# colorCube64_led1.net
KiCad netlist of a schematic drawn in EAGLE
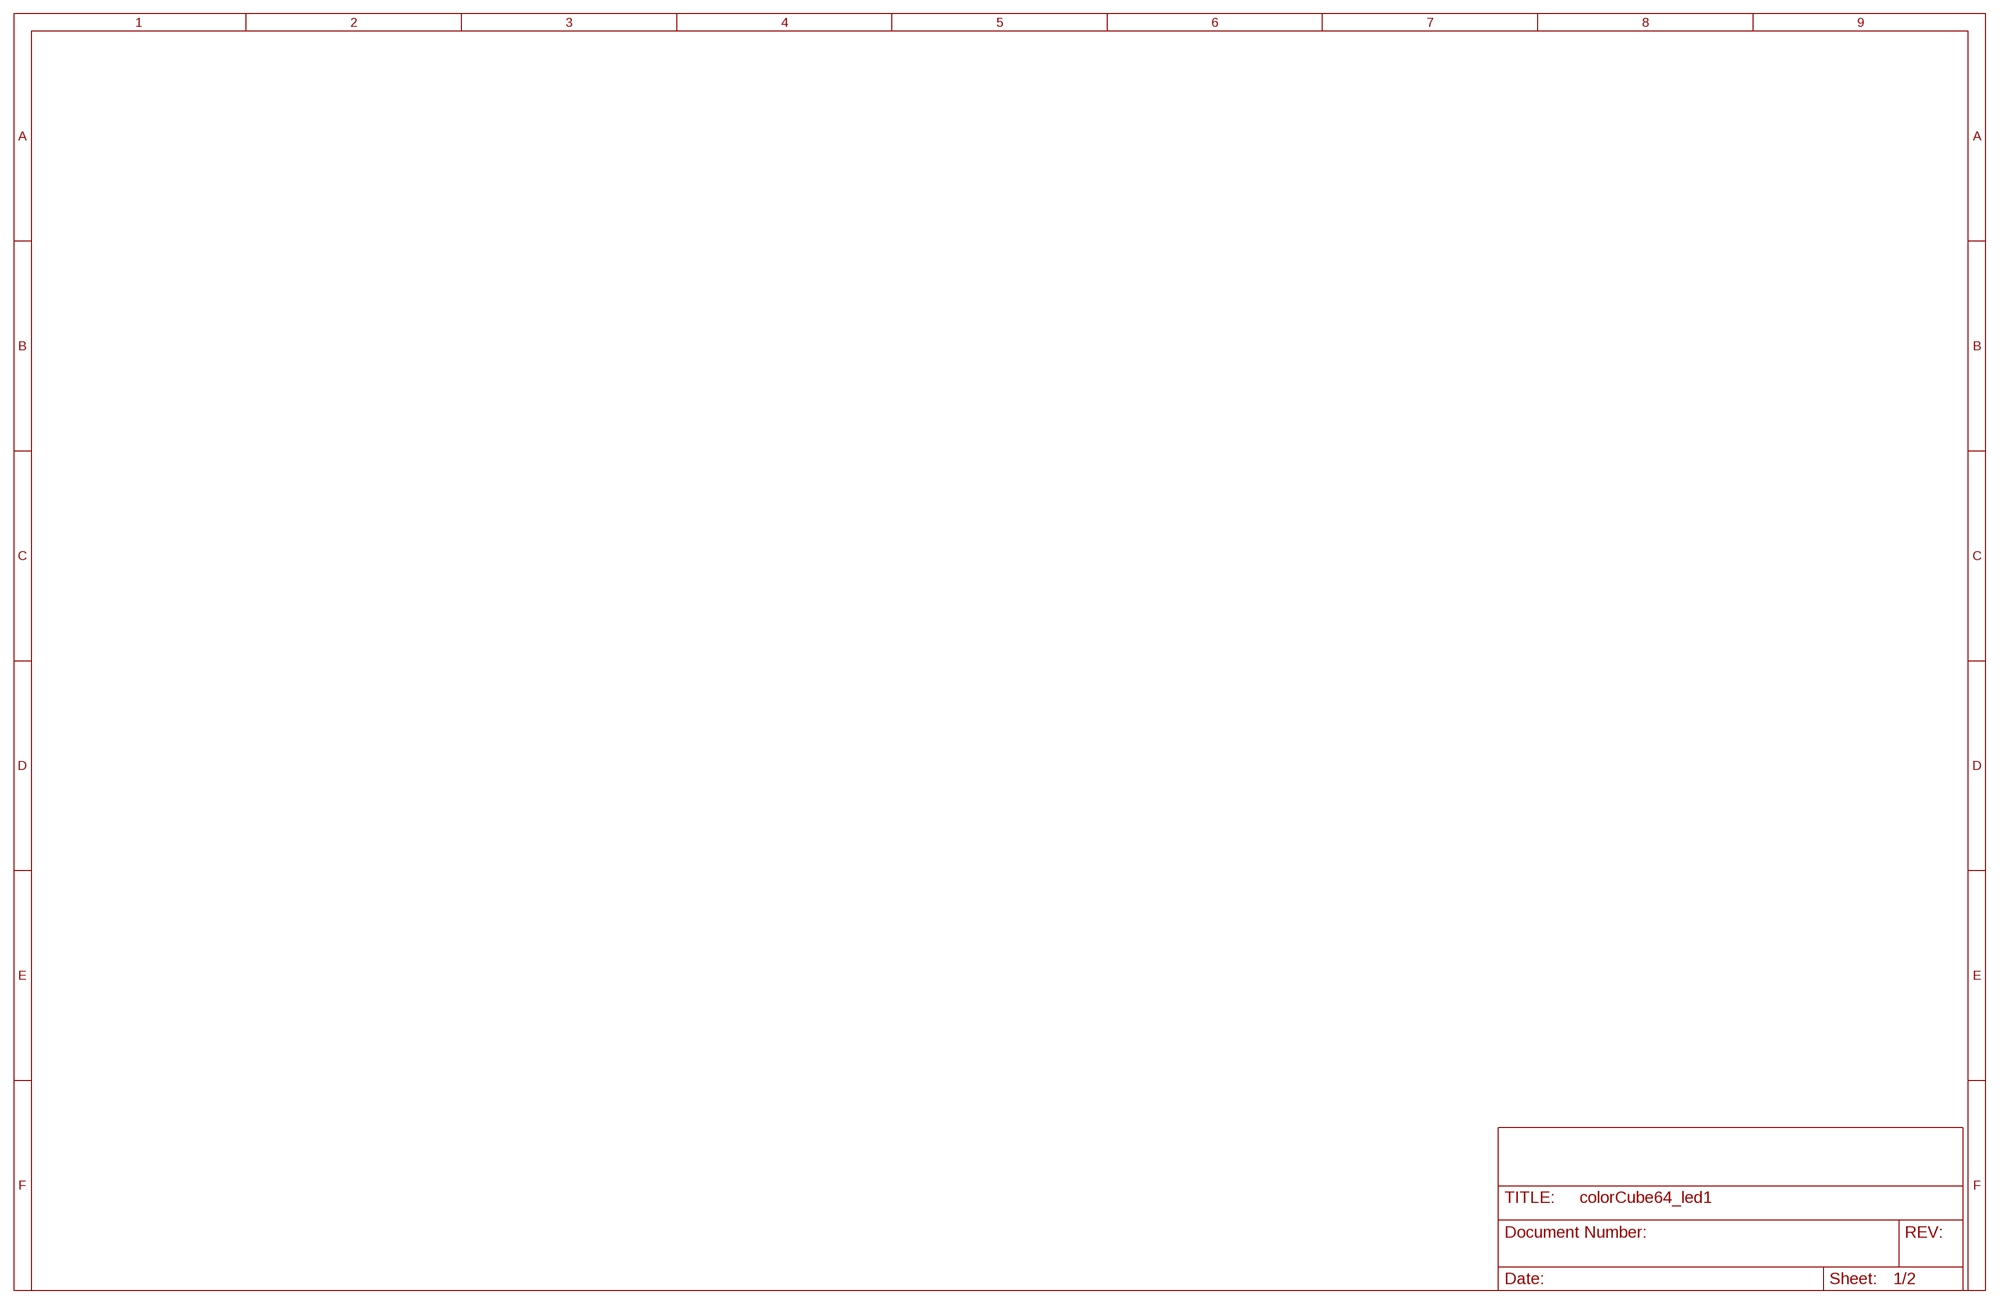
[diagram p0: schematic, sheet 1]
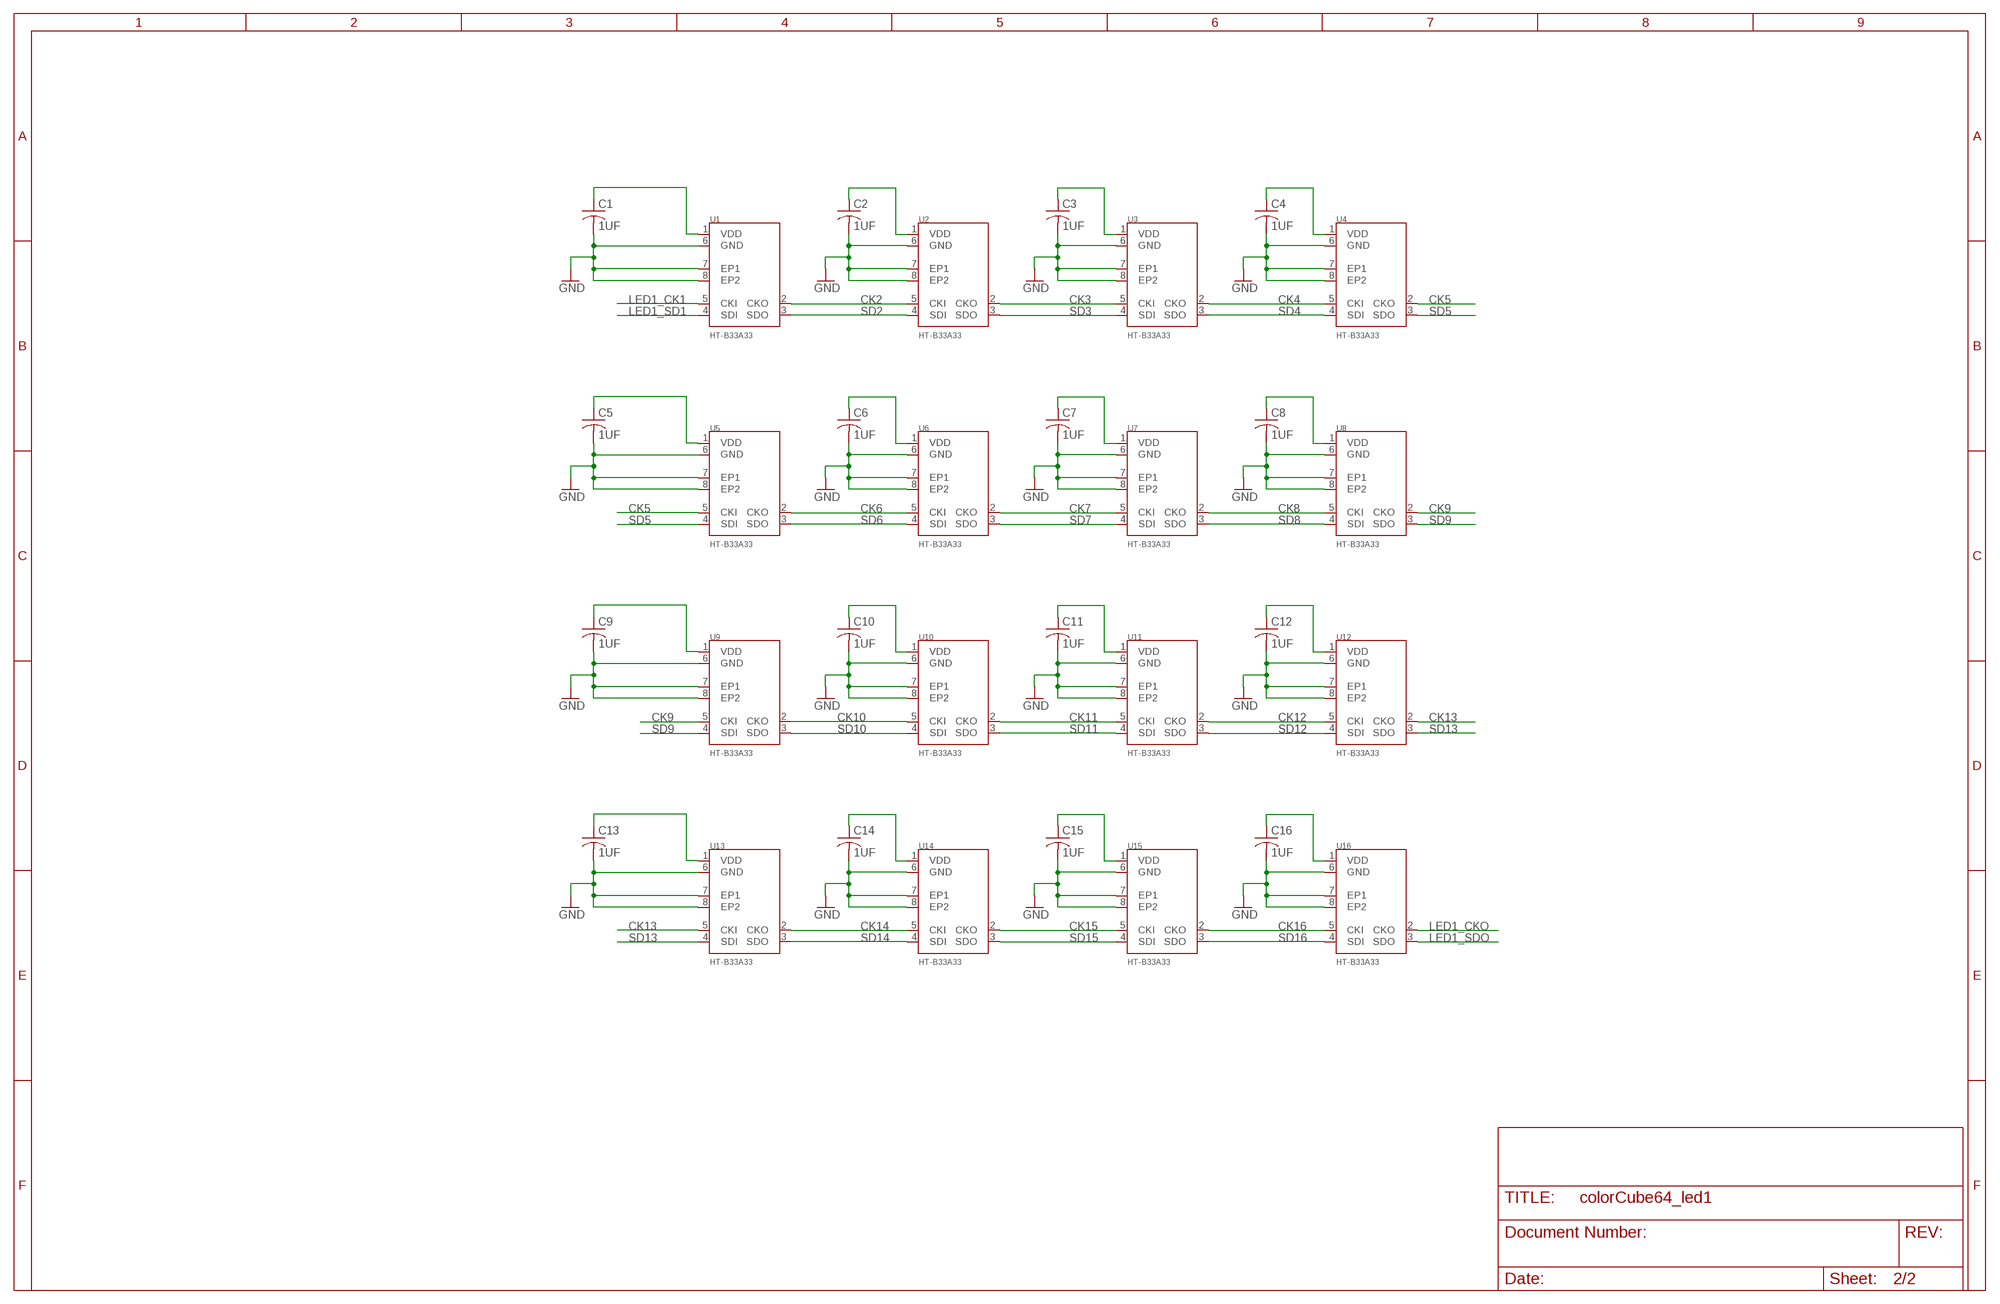
[diagram p1: schematic, sheet 2]

(export (version "E")
  (design (tool "Eeschema 10.0.6"))
  (components
    (comp (ref "C1")
      (value "1UF")
      (footprint "eagle-import:C0201")
      (libsource (lib "eagle-import") (part "C-USC0201"))
    )
    (comp (ref "C2")
      (value "1UF")
      (footprint "eagle-import:C0201")
      (libsource (lib "eagle-import") (part "C-USC0201"))
    )
    (comp (ref "C3")
      (value "1UF")
      (footprint "eagle-import:C0201")
      (libsource (lib "eagle-import") (part "C-USC0201"))
    )
    (comp (ref "C4")
      (value "1UF")
      (footprint "eagle-import:C0201")
      (libsource (lib "eagle-import") (part "C-USC0201"))
    )
    (comp (ref "C5")
      (value "1UF")
      (footprint "eagle-import:C0201")
      (libsource (lib "eagle-import") (part "C-USC0201"))
    )
    (comp (ref "C6")
      (value "1UF")
      (footprint "eagle-import:C0201")
      (libsource (lib "eagle-import") (part "C-USC0201"))
    )
    (comp (ref "C7")
      (value "1UF")
      (footprint "eagle-import:C0201")
      (libsource (lib "eagle-import") (part "C-USC0201"))
    )
    (comp (ref "C8")
      (value "1UF")
      (footprint "eagle-import:C0201")
      (libsource (lib "eagle-import") (part "C-USC0201"))
    )
    (comp (ref "C9")
      (value "1UF")
      (footprint "eagle-import:C0201")
      (libsource (lib "eagle-import") (part "C-USC0201"))
    )
    (comp (ref "C10")
      (value "1UF")
      (footprint "eagle-import:C0201")
      (libsource (lib "eagle-import") (part "C-USC0201"))
    )
    (comp (ref "C11")
      (value "1UF")
      (footprint "eagle-import:C0201")
      (libsource (lib "eagle-import") (part "C-USC0201"))
    )
    (comp (ref "C12")
      (value "1UF")
      (footprint "eagle-import:C0201")
      (libsource (lib "eagle-import") (part "C-USC0201"))
    )
    (comp (ref "C13")
      (value "1UF")
      (footprint "eagle-import:C0201")
      (libsource (lib "eagle-import") (part "C-USC0201"))
    )
    (comp (ref "C14")
      (value "1UF")
      (footprint "eagle-import:C0201")
      (libsource (lib "eagle-import") (part "C-USC0201"))
    )
    (comp (ref "C15")
      (value "1UF")
      (footprint "eagle-import:C0201")
      (libsource (lib "eagle-import") (part "C-USC0201"))
    )
    (comp (ref "C16")
      (value "1UF")
      (footprint "eagle-import:C0201")
      (libsource (lib "eagle-import") (part "C-USC0201"))
    )
    (comp (ref "U1")
      (value "HT-B33A33")
      (footprint "eagle-import:HT-B33A3")
      (libsource (lib "eagle-import") (part "HT-B33A33"))
    )
    (comp (ref "U2")
      (value "HT-B33A33")
      (footprint "eagle-import:HT-B33A3")
      (libsource (lib "eagle-import") (part "HT-B33A33"))
    )
    (comp (ref "U3")
      (value "HT-B33A33")
      (footprint "eagle-import:HT-B33A3")
      (libsource (lib "eagle-import") (part "HT-B33A33"))
    )
    (comp (ref "U4")
      (value "HT-B33A33")
      (footprint "eagle-import:HT-B33A3")
      (libsource (lib "eagle-import") (part "HT-B33A33"))
    )
    (comp (ref "U5")
      (value "HT-B33A33")
      (footprint "eagle-import:HT-B33A3")
      (libsource (lib "eagle-import") (part "HT-B33A33"))
    )
    (comp (ref "U6")
      (value "HT-B33A33")
      (footprint "eagle-import:HT-B33A3")
      (libsource (lib "eagle-import") (part "HT-B33A33"))
    )
    (comp (ref "U7")
      (value "HT-B33A33")
      (footprint "eagle-import:HT-B33A3")
      (libsource (lib "eagle-import") (part "HT-B33A33"))
    )
    (comp (ref "U8")
      (value "HT-B33A33")
      (footprint "eagle-import:HT-B33A3")
      (libsource (lib "eagle-import") (part "HT-B33A33"))
    )
    (comp (ref "U9")
      (value "HT-B33A33")
      (footprint "eagle-import:HT-B33A3")
      (libsource (lib "eagle-import") (part "HT-B33A33"))
    )
    (comp (ref "U10")
      (value "HT-B33A33")
      (footprint "eagle-import:HT-B33A3")
      (libsource (lib "eagle-import") (part "HT-B33A33"))
    )
    (comp (ref "U11")
      (value "HT-B33A33")
      (footprint "eagle-import:HT-B33A3")
      (libsource (lib "eagle-import") (part "HT-B33A33"))
    )
    (comp (ref "U12")
      (value "HT-B33A33")
      (footprint "eagle-import:HT-B33A3")
      (libsource (lib "eagle-import") (part "HT-B33A33"))
    )
    (comp (ref "U13")
      (value "HT-B33A33")
      (footprint "eagle-import:HT-B33A3")
      (libsource (lib "eagle-import") (part "HT-B33A33"))
    )
    (comp (ref "U14")
      (value "HT-B33A33")
      (footprint "eagle-import:HT-B33A3")
      (libsource (lib "eagle-import") (part "HT-B33A33"))
    )
    (comp (ref "U15")
      (value "HT-B33A33")
      (footprint "eagle-import:HT-B33A3")
      (libsource (lib "eagle-import") (part "HT-B33A33"))
    )
    (comp (ref "U16")
      (value "HT-B33A33")
      (footprint "eagle-import:HT-B33A3")
      (libsource (lib "eagle-import") (part "HT-B33A33"))
    )
  )
  (nets
    (net (code "1") (name "CK2") (class "Default")
      (node (ref "U1") (pin "2") (pinfunction "CKO_2") (pintype "bidirectional"))
      (node (ref "U2") (pin "5") (pinfunction "CKI_5") (pintype "bidirectional"))
    )
    (net (code "2") (name "CK3") (class "Default")
      (node (ref "U2") (pin "2") (pinfunction "CKO_2") (pintype "bidirectional"))
      (node (ref "U3") (pin "5") (pinfunction "CKI_5") (pintype "bidirectional"))
    )
    (net (code "3") (name "CK4") (class "Default")
      (node (ref "U3") (pin "2") (pinfunction "CKO_2") (pintype "bidirectional"))
      (node (ref "U4") (pin "5") (pinfunction "CKI_5") (pintype "bidirectional"))
    )
    (net (code "4") (name "CK5") (class "Default")
      (node (ref "U4") (pin "2") (pinfunction "CKO_2") (pintype "bidirectional"))
      (node (ref "U5") (pin "5") (pinfunction "CKI_5") (pintype "bidirectional"))
    )
    (net (code "5") (name "CK6") (class "Default")
      (node (ref "U5") (pin "2") (pinfunction "CKO_2") (pintype "bidirectional"))
      (node (ref "U6") (pin "5") (pinfunction "CKI_5") (pintype "bidirectional"))
    )
    (net (code "6") (name "CK7") (class "Default")
      (node (ref "U6") (pin "2") (pinfunction "CKO_2") (pintype "bidirectional"))
      (node (ref "U7") (pin "5") (pinfunction "CKI_5") (pintype "bidirectional"))
    )
    (net (code "7") (name "CK8") (class "Default")
      (node (ref "U7") (pin "2") (pinfunction "CKO_2") (pintype "bidirectional"))
      (node (ref "U8") (pin "5") (pinfunction "CKI_5") (pintype "bidirectional"))
    )
    (net (code "8") (name "CK9") (class "Default")
      (node (ref "U8") (pin "2") (pinfunction "CKO_2") (pintype "bidirectional"))
      (node (ref "U9") (pin "5") (pinfunction "CKI_5") (pintype "bidirectional"))
    )
    (net (code "9") (name "CK10") (class "Default")
      (node (ref "U10") (pin "5") (pinfunction "CKI_5") (pintype "bidirectional"))
      (node (ref "U9") (pin "2") (pinfunction "CKO_2") (pintype "bidirectional"))
    )
    (net (code "10") (name "CK11") (class "Default")
      (node (ref "U10") (pin "2") (pinfunction "CKO_2") (pintype "bidirectional"))
      (node (ref "U11") (pin "5") (pinfunction "CKI_5") (pintype "bidirectional"))
    )
    (net (code "11") (name "CK12") (class "Default")
      (node (ref "U11") (pin "2") (pinfunction "CKO_2") (pintype "bidirectional"))
      (node (ref "U12") (pin "5") (pinfunction "CKI_5") (pintype "bidirectional"))
    )
    (net (code "12") (name "CK13") (class "Default")
      (node (ref "U12") (pin "2") (pinfunction "CKO_2") (pintype "bidirectional"))
      (node (ref "U13") (pin "5") (pinfunction "CKI_5") (pintype "bidirectional"))
    )
    (net (code "13") (name "CK14") (class "Default")
      (node (ref "U13") (pin "2") (pinfunction "CKO_2") (pintype "bidirectional"))
      (node (ref "U14") (pin "5") (pinfunction "CKI_5") (pintype "bidirectional"))
    )
    (net (code "14") (name "CK15") (class "Default")
      (node (ref "U14") (pin "2") (pinfunction "CKO_2") (pintype "bidirectional"))
      (node (ref "U15") (pin "5") (pinfunction "CKI_5") (pintype "bidirectional"))
    )
    (net (code "15") (name "CK16") (class "Default")
      (node (ref "U15") (pin "2") (pinfunction "CKO_2") (pintype "bidirectional"))
      (node (ref "U16") (pin "5") (pinfunction "CKI_5") (pintype "bidirectional"))
    )
    (net (code "16") (name "GND") (class "Default")
      (node (ref "C1") (pin "2") (pinfunction "2_2") (pintype "passive"))
      (node (ref "C10") (pin "2") (pinfunction "2_2") (pintype "passive"))
      (node (ref "C11") (pin "2") (pinfunction "2_2") (pintype "passive"))
      (node (ref "C12") (pin "2") (pinfunction "2_2") (pintype "passive"))
      (node (ref "C13") (pin "2") (pinfunction "2_2") (pintype "passive"))
      (node (ref "C14") (pin "2") (pinfunction "2_2") (pintype "passive"))
      (node (ref "C15") (pin "2") (pinfunction "2_2") (pintype "passive"))
      (node (ref "C16") (pin "2") (pinfunction "2_2") (pintype "passive"))
      (node (ref "C2") (pin "2") (pinfunction "2_2") (pintype "passive"))
      (node (ref "C3") (pin "2") (pinfunction "2_2") (pintype "passive"))
      (node (ref "C4") (pin "2") (pinfunction "2_2") (pintype "passive"))
      (node (ref "C5") (pin "2") (pinfunction "2_2") (pintype "passive"))
      (node (ref "C6") (pin "2") (pinfunction "2_2") (pintype "passive"))
      (node (ref "C7") (pin "2") (pinfunction "2_2") (pintype "passive"))
      (node (ref "C8") (pin "2") (pinfunction "2_2") (pintype "passive"))
      (node (ref "C9") (pin "2") (pinfunction "2_2") (pintype "passive"))
      (node (ref "U1") (pin "6") (pinfunction "GND_6") (pintype "bidirectional"))
      (node (ref "U1") (pin "7") (pinfunction "EP1_7") (pintype "bidirectional"))
      (node (ref "U1") (pin "8") (pinfunction "EP2_8") (pintype "bidirectional"))
      (node (ref "U10") (pin "6") (pinfunction "GND_6") (pintype "bidirectional"))
      (node (ref "U10") (pin "7") (pinfunction "EP1_7") (pintype "bidirectional"))
      (node (ref "U10") (pin "8") (pinfunction "EP2_8") (pintype "bidirectional"))
      (node (ref "U11") (pin "6") (pinfunction "GND_6") (pintype "bidirectional"))
      (node (ref "U11") (pin "7") (pinfunction "EP1_7") (pintype "bidirectional"))
      (node (ref "U11") (pin "8") (pinfunction "EP2_8") (pintype "bidirectional"))
      (node (ref "U12") (pin "6") (pinfunction "GND_6") (pintype "bidirectional"))
      (node (ref "U12") (pin "7") (pinfunction "EP1_7") (pintype "bidirectional"))
      (node (ref "U12") (pin "8") (pinfunction "EP2_8") (pintype "bidirectional"))
      (node (ref "U13") (pin "6") (pinfunction "GND_6") (pintype "bidirectional"))
      (node (ref "U13") (pin "7") (pinfunction "EP1_7") (pintype "bidirectional"))
      (node (ref "U13") (pin "8") (pinfunction "EP2_8") (pintype "bidirectional"))
      (node (ref "U14") (pin "6") (pinfunction "GND_6") (pintype "bidirectional"))
      (node (ref "U14") (pin "7") (pinfunction "EP1_7") (pintype "bidirectional"))
      (node (ref "U14") (pin "8") (pinfunction "EP2_8") (pintype "bidirectional"))
      (node (ref "U15") (pin "6") (pinfunction "GND_6") (pintype "bidirectional"))
      (node (ref "U15") (pin "7") (pinfunction "EP1_7") (pintype "bidirectional"))
      (node (ref "U15") (pin "8") (pinfunction "EP2_8") (pintype "bidirectional"))
      (node (ref "U16") (pin "6") (pinfunction "GND_6") (pintype "bidirectional"))
      (node (ref "U16") (pin "7") (pinfunction "EP1_7") (pintype "bidirectional"))
      (node (ref "U16") (pin "8") (pinfunction "EP2_8") (pintype "bidirectional"))
      (node (ref "U2") (pin "6") (pinfunction "GND_6") (pintype "bidirectional"))
      (node (ref "U2") (pin "7") (pinfunction "EP1_7") (pintype "bidirectional"))
      (node (ref "U2") (pin "8") (pinfunction "EP2_8") (pintype "bidirectional"))
      (node (ref "U3") (pin "6") (pinfunction "GND_6") (pintype "bidirectional"))
      (node (ref "U3") (pin "7") (pinfunction "EP1_7") (pintype "bidirectional"))
      (node (ref "U3") (pin "8") (pinfunction "EP2_8") (pintype "bidirectional"))
      (node (ref "U4") (pin "6") (pinfunction "GND_6") (pintype "bidirectional"))
      (node (ref "U4") (pin "7") (pinfunction "EP1_7") (pintype "bidirectional"))
      (node (ref "U4") (pin "8") (pinfunction "EP2_8") (pintype "bidirectional"))
      (node (ref "U5") (pin "6") (pinfunction "GND_6") (pintype "bidirectional"))
      (node (ref "U5") (pin "7") (pinfunction "EP1_7") (pintype "bidirectional"))
      (node (ref "U5") (pin "8") (pinfunction "EP2_8") (pintype "bidirectional"))
      (node (ref "U6") (pin "6") (pinfunction "GND_6") (pintype "bidirectional"))
      (node (ref "U6") (pin "7") (pinfunction "EP1_7") (pintype "bidirectional"))
      (node (ref "U6") (pin "8") (pinfunction "EP2_8") (pintype "bidirectional"))
      (node (ref "U7") (pin "6") (pinfunction "GND_6") (pintype "bidirectional"))
      (node (ref "U7") (pin "7") (pinfunction "EP1_7") (pintype "bidirectional"))
      (node (ref "U7") (pin "8") (pinfunction "EP2_8") (pintype "bidirectional"))
      (node (ref "U8") (pin "6") (pinfunction "GND_6") (pintype "bidirectional"))
      (node (ref "U8") (pin "7") (pinfunction "EP1_7") (pintype "bidirectional"))
      (node (ref "U8") (pin "8") (pinfunction "EP2_8") (pintype "bidirectional"))
      (node (ref "U9") (pin "6") (pinfunction "GND_6") (pintype "bidirectional"))
      (node (ref "U9") (pin "7") (pinfunction "EP1_7") (pintype "bidirectional"))
      (node (ref "U9") (pin "8") (pinfunction "EP2_8") (pintype "bidirectional"))
    )
    (net (code "17") (name "LED1_CK1") (class "Default")
      (node (ref "U1") (pin "5") (pinfunction "CKI_5") (pintype "bidirectional"))
    )
    (net (code "18") (name "LED1_CKO") (class "Default")
      (node (ref "U16") (pin "2") (pinfunction "CKO_2") (pintype "bidirectional"))
    )
    (net (code "19") (name "LED1_SD1") (class "Default")
      (node (ref "U1") (pin "4") (pinfunction "SDI_4") (pintype "bidirectional"))
    )
    (net (code "20") (name "LED1_SDO") (class "Default")
      (node (ref "U16") (pin "3") (pinfunction "SDO_3") (pintype "bidirectional"))
    )
    (net (code "21") (name "Net-(U1-VDD)") (class "Default")
      (node (ref "C1") (pin "1") (pinfunction "1_1") (pintype "passive"))
      (node (ref "U1") (pin "1") (pinfunction "VDD_1") (pintype "bidirectional"))
    )
    (net (code "22") (name "Net-(U2-VDD)") (class "Default")
      (node (ref "C2") (pin "1") (pinfunction "1_1") (pintype "passive"))
      (node (ref "U2") (pin "1") (pinfunction "VDD_1") (pintype "bidirectional"))
    )
    (net (code "23") (name "Net-(U3-VDD)") (class "Default")
      (node (ref "C3") (pin "1") (pinfunction "1_1") (pintype "passive"))
      (node (ref "U3") (pin "1") (pinfunction "VDD_1") (pintype "bidirectional"))
    )
    (net (code "24") (name "Net-(U4-VDD)") (class "Default")
      (node (ref "C4") (pin "1") (pinfunction "1_1") (pintype "passive"))
      (node (ref "U4") (pin "1") (pinfunction "VDD_1") (pintype "bidirectional"))
    )
    (net (code "25") (name "Net-(U5-VDD)") (class "Default")
      (node (ref "C5") (pin "1") (pinfunction "1_1") (pintype "passive"))
      (node (ref "U5") (pin "1") (pinfunction "VDD_1") (pintype "bidirectional"))
    )
    (net (code "26") (name "Net-(U6-VDD)") (class "Default")
      (node (ref "C6") (pin "1") (pinfunction "1_1") (pintype "passive"))
      (node (ref "U6") (pin "1") (pinfunction "VDD_1") (pintype "bidirectional"))
    )
    (net (code "27") (name "Net-(U7-VDD)") (class "Default")
      (node (ref "C7") (pin "1") (pinfunction "1_1") (pintype "passive"))
      (node (ref "U7") (pin "1") (pinfunction "VDD_1") (pintype "bidirectional"))
    )
    (net (code "28") (name "Net-(U8-VDD)") (class "Default")
      (node (ref "C8") (pin "1") (pinfunction "1_1") (pintype "passive"))
      (node (ref "U8") (pin "1") (pinfunction "VDD_1") (pintype "bidirectional"))
    )
    (net (code "29") (name "Net-(U9-VDD)") (class "Default")
      (node (ref "C9") (pin "1") (pinfunction "1_1") (pintype "passive"))
      (node (ref "U9") (pin "1") (pinfunction "VDD_1") (pintype "bidirectional"))
    )
    (net (code "30") (name "Net-(U10-VDD)") (class "Default")
      (node (ref "C10") (pin "1") (pinfunction "1_1") (pintype "passive"))
      (node (ref "U10") (pin "1") (pinfunction "VDD_1") (pintype "bidirectional"))
    )
    (net (code "31") (name "Net-(U11-VDD)") (class "Default")
      (node (ref "C11") (pin "1") (pinfunction "1_1") (pintype "passive"))
      (node (ref "U11") (pin "1") (pinfunction "VDD_1") (pintype "bidirectional"))
    )
    (net (code "32") (name "Net-(U12-VDD)") (class "Default")
      (node (ref "C12") (pin "1") (pinfunction "1_1") (pintype "passive"))
      (node (ref "U12") (pin "1") (pinfunction "VDD_1") (pintype "bidirectional"))
    )
    (net (code "33") (name "Net-(U13-VDD)") (class "Default")
      (node (ref "C13") (pin "1") (pinfunction "1_1") (pintype "passive"))
      (node (ref "U13") (pin "1") (pinfunction "VDD_1") (pintype "bidirectional"))
    )
    (net (code "34") (name "Net-(U14-VDD)") (class "Default")
      (node (ref "C14") (pin "1") (pinfunction "1_1") (pintype "passive"))
      (node (ref "U14") (pin "1") (pinfunction "VDD_1") (pintype "bidirectional"))
    )
    (net (code "35") (name "Net-(U15-VDD)") (class "Default")
      (node (ref "C15") (pin "1") (pinfunction "1_1") (pintype "passive"))
      (node (ref "U15") (pin "1") (pinfunction "VDD_1") (pintype "bidirectional"))
    )
    (net (code "36") (name "Net-(U16-VDD)") (class "Default")
      (node (ref "C16") (pin "1") (pinfunction "1_1") (pintype "passive"))
      (node (ref "U16") (pin "1") (pinfunction "VDD_1") (pintype "bidirectional"))
    )
    (net (code "37") (name "SD2") (class "Default")
      (node (ref "U1") (pin "3") (pinfunction "SDO_3") (pintype "bidirectional"))
      (node (ref "U2") (pin "4") (pinfunction "SDI_4") (pintype "bidirectional"))
    )
    (net (code "38") (name "SD3") (class "Default")
      (node (ref "U2") (pin "3") (pinfunction "SDO_3") (pintype "bidirectional"))
      (node (ref "U3") (pin "4") (pinfunction "SDI_4") (pintype "bidirectional"))
    )
    (net (code "39") (name "SD4") (class "Default")
      (node (ref "U3") (pin "3") (pinfunction "SDO_3") (pintype "bidirectional"))
      (node (ref "U4") (pin "4") (pinfunction "SDI_4") (pintype "bidirectional"))
    )
    (net (code "40") (name "SD5") (class "Default")
      (node (ref "U4") (pin "3") (pinfunction "SDO_3") (pintype "bidirectional"))
      (node (ref "U5") (pin "4") (pinfunction "SDI_4") (pintype "bidirectional"))
    )
    (net (code "41") (name "SD6") (class "Default")
      (node (ref "U5") (pin "3") (pinfunction "SDO_3") (pintype "bidirectional"))
      (node (ref "U6") (pin "4") (pinfunction "SDI_4") (pintype "bidirectional"))
    )
    (net (code "42") (name "SD7") (class "Default")
      (node (ref "U6") (pin "3") (pinfunction "SDO_3") (pintype "bidirectional"))
      (node (ref "U7") (pin "4") (pinfunction "SDI_4") (pintype "bidirectional"))
    )
    (net (code "43") (name "SD8") (class "Default")
      (node (ref "U7") (pin "3") (pinfunction "SDO_3") (pintype "bidirectional"))
      (node (ref "U8") (pin "4") (pinfunction "SDI_4") (pintype "bidirectional"))
    )
    (net (code "44") (name "SD9") (class "Default")
      (node (ref "U8") (pin "3") (pinfunction "SDO_3") (pintype "bidirectional"))
      (node (ref "U9") (pin "4") (pinfunction "SDI_4") (pintype "bidirectional"))
    )
    (net (code "45") (name "SD10") (class "Default")
      (node (ref "U10") (pin "4") (pinfunction "SDI_4") (pintype "bidirectional"))
      (node (ref "U9") (pin "3") (pinfunction "SDO_3") (pintype "bidirectional"))
    )
    (net (code "46") (name "SD11") (class "Default")
      (node (ref "U10") (pin "3") (pinfunction "SDO_3") (pintype "bidirectional"))
      (node (ref "U11") (pin "4") (pinfunction "SDI_4") (pintype "bidirectional"))
    )
    (net (code "47") (name "SD12") (class "Default")
      (node (ref "U11") (pin "3") (pinfunction "SDO_3") (pintype "bidirectional"))
      (node (ref "U12") (pin "4") (pinfunction "SDI_4") (pintype "bidirectional"))
    )
    (net (code "48") (name "SD13") (class "Default")
      (node (ref "U12") (pin "3") (pinfunction "SDO_3") (pintype "bidirectional"))
      (node (ref "U13") (pin "4") (pinfunction "SDI_4") (pintype "bidirectional"))
    )
    (net (code "49") (name "SD14") (class "Default")
      (node (ref "U13") (pin "3") (pinfunction "SDO_3") (pintype "bidirectional"))
      (node (ref "U14") (pin "4") (pinfunction "SDI_4") (pintype "bidirectional"))
    )
    (net (code "50") (name "SD15") (class "Default")
      (node (ref "U14") (pin "3") (pinfunction "SDO_3") (pintype "bidirectional"))
      (node (ref "U15") (pin "4") (pinfunction "SDI_4") (pintype "bidirectional"))
    )
    (net (code "51") (name "SD16") (class "Default")
      (node (ref "U15") (pin "3") (pinfunction "SDO_3") (pintype "bidirectional"))
      (node (ref "U16") (pin "4") (pinfunction "SDI_4") (pintype "bidirectional"))
    )
  )
)
